# Alarm.net
KiCad netlist of a schematic drawn in Altium Designer
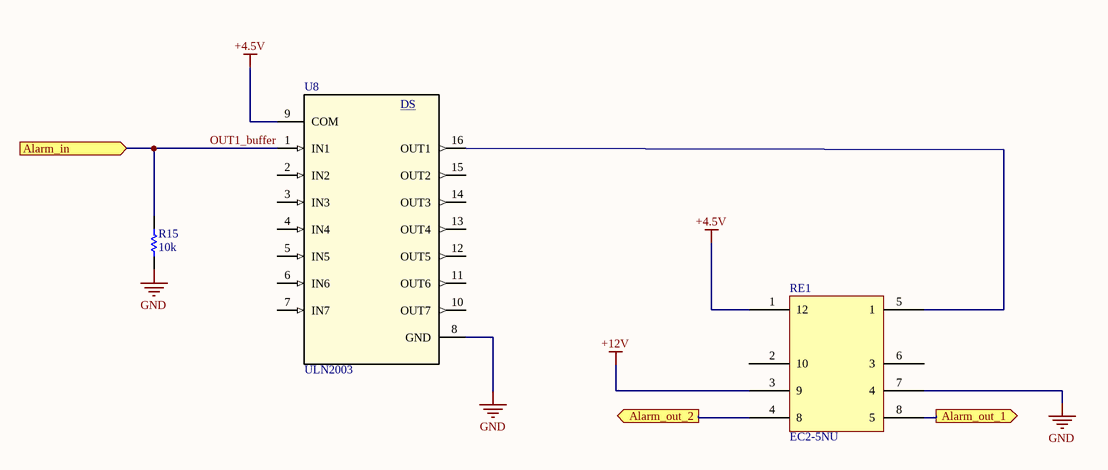
[diagram p0: Alarm.SchDoc]

(export (version "E")
  (design (tool "Eeschema 10.0.6"))
  (components
    (comp (ref "R15")
      (value "10k")
      (footprint "R-805")
      (description "Resistor")
      (fields (field (name "Comment") "R-805"))
      (libsource (lib "AfraLIB") (part "R-805"))
    )
    (comp (ref "RE1") (value "EC2-5NU") (footprint "EC2-5NU") (libsource (lib "AfraLIB") (part "EC2_5NU")))
    (comp (ref "U8")
      (value "ULN2003")
      (footprint "ULN20003")
      (description "No Description Available")
      (fields
        (field (name "PARTNUMBER") "ULN2003ADR")
        (field (name "MANUFACTURER") "Texas Instruments")
        (field (name "COPYRIGHT") "Copyright (C) 2018 Accelerated Designs. All rights reserved")
      )
      (libsource (lib "AfraLIB") (part "ULN2003"))
    )
  )
  (nets
    (net (code "1") (name "+4.5V") (class "Default")
      (node (ref "RE1") (pin "1") (pinfunction "12_1") (pintype "passive"))
      (node (ref "U8") (pin "9") (pinfunction "COM_9") (pintype "power_in"))
    )
    (net (code "2") (name "+12V") (class "Default")
      (node (ref "RE1") (pin "3") (pinfunction "9_3") (pintype "passive"))
    )
    (net (code "3") (name "/Alarm_out_1") (class "Default")
      (node (ref "RE1") (pin "8") (pinfunction "5_8") (pintype "passive"))
    )
    (net (code "4") (name "/Alarm_out_2") (class "Default")
      (node (ref "RE1") (pin "4") (pinfunction "8_4") (pintype "passive"))
    )
    (net (code "5") (name "/OUT1_buffer") (class "Default")
      (node (ref "R15") (pin "2") (pinfunction "2_2") (pintype "passive"))
      (node (ref "U8") (pin "1") (pinfunction "IN1_1") (pintype "input"))
    )
    (net (code "6") (name "GND") (class "Default")
      (node (ref "R15") (pin "1") (pinfunction "1_1") (pintype "passive"))
      (node (ref "RE1") (pin "7") (pinfunction "4_7") (pintype "passive"))
      (node (ref "U8") (pin "8") (pinfunction "GND_8") (pintype "power_in"))
    )
    (net (code "7") (name "Net-(RE1-1)") (class "Default")
      (node (ref "RE1") (pin "5") (pinfunction "1_5") (pintype "passive"))
      (node (ref "U8") (pin "16") (pinfunction "OUT1_16") (pintype "output"))
    )
    (net (code "8") (name "unconnected-(RE1-3-Pad6)") (class "Default")
      (node (ref "RE1") (pin "6") (pinfunction "3_6") (pintype "passive"))
    )
    (net (code "9") (name "unconnected-(RE1-10-Pad2)") (class "Default")
      (node (ref "RE1") (pin "2") (pinfunction "10_2") (pintype "passive"))
    )
    (net (code "10") (name "unconnected-(U8-IN2-Pad2)") (class "Default")
      (node (ref "U8") (pin "2") (pinfunction "IN2_2") (pintype "input"))
    )
    (net (code "11") (name "unconnected-(U8-IN3-Pad3)") (class "Default")
      (node (ref "U8") (pin "3") (pinfunction "IN3_3") (pintype "input"))
    )
    (net (code "12") (name "unconnected-(U8-IN4-Pad4)") (class "Default")
      (node (ref "U8") (pin "4") (pinfunction "IN4_4") (pintype "input"))
    )
    (net (code "13") (name "unconnected-(U8-IN5-Pad5)") (class "Default")
      (node (ref "U8") (pin "5") (pinfunction "IN5_5") (pintype "input"))
    )
    (net (code "14") (name "unconnected-(U8-IN6-Pad6)") (class "Default")
      (node (ref "U8") (pin "6") (pinfunction "IN6_6") (pintype "input"))
    )
    (net (code "15") (name "unconnected-(U8-IN7-Pad7)") (class "Default")
      (node (ref "U8") (pin "7") (pinfunction "IN7_7") (pintype "input"))
    )
    (net (code "16") (name "unconnected-(U8-OUT2-Pad15)") (class "Default")
      (node (ref "U8") (pin "15") (pinfunction "OUT2_15") (pintype "output"))
    )
    (net (code "17") (name "unconnected-(U8-OUT3-Pad14)") (class "Default")
      (node (ref "U8") (pin "14") (pinfunction "OUT3_14") (pintype "output"))
    )
    (net (code "18") (name "unconnected-(U8-OUT4-Pad13)") (class "Default")
      (node (ref "U8") (pin "13") (pinfunction "OUT4_13") (pintype "output"))
    )
    (net (code "19") (name "unconnected-(U8-OUT5-Pad12)") (class "Default")
      (node (ref "U8") (pin "12") (pinfunction "OUT5_12") (pintype "output"))
    )
    (net (code "20") (name "unconnected-(U8-OUT6-Pad11)") (class "Default")
      (node (ref "U8") (pin "11") (pinfunction "OUT6_11") (pintype "output"))
    )
    (net (code "21") (name "unconnected-(U8-OUT7-Pad10)") (class "Default")
      (node (ref "U8") (pin "10") (pinfunction "OUT7_10") (pintype "output"))
    )
  )
)
